# MiL-Driver.net
KiCad netlist of a schematic drawn in EAGLE
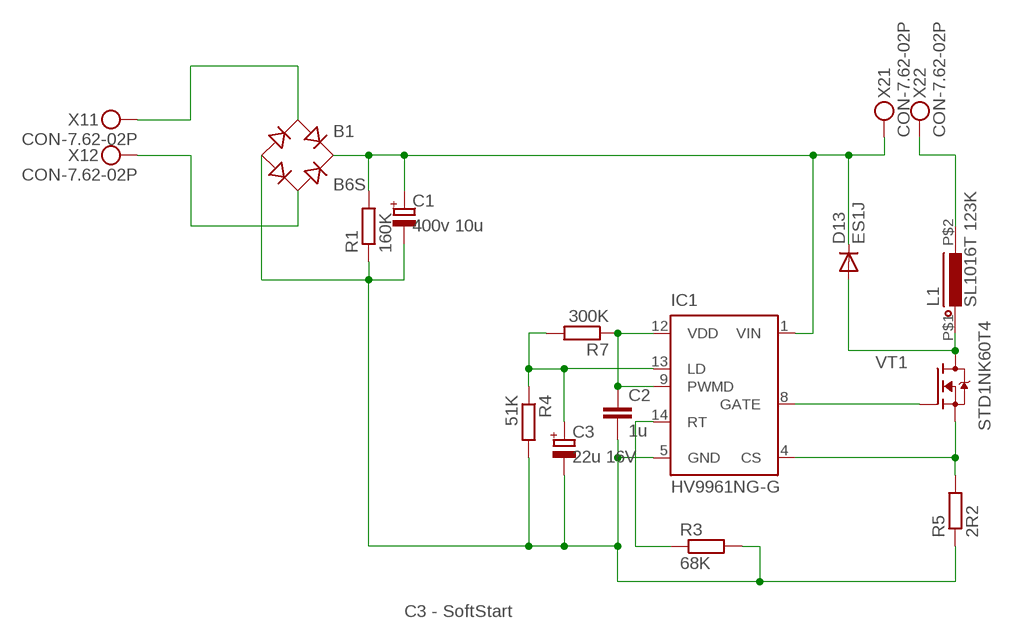
[diagram p0: schematic, sheet 1]

(export (version "E")
  (design (tool "Eeschema 10.0.6"))
  (components
    (comp (ref "B1")
      (value "B6S")
      (footprint "eagle-import:MBS")
      (libsource (lib "eagle-import") (part "BS6"))
    )
    (comp (ref "C1")
      (value "400v 10u")
      (footprint "eagle-import:E3,5-8")
      (libsource (lib "eagle-import") (part "CAP-POL_E3.5-8"))
    )
    (comp (ref "C2")
      (value "1u")
      (footprint "eagle-import:C0805")
      (libsource (lib "eagle-import") (part "CAP_0805"))
    )
    (comp (ref "C3")
      (value "22u 16V")
      (footprint "eagle-import:E2,5-7")
      (libsource (lib "eagle-import") (part "CAP-POL_E2.5-7"))
    )
    (comp (ref "D13")
      (value "ES1J")
      (footprint "eagle-import:DO214AC")
      (libsource (lib "eagle-import") (part "DIODE_ES1J"))
    )
    (comp (ref "IC1")
      (value "HV9961NG-G")
      (footprint "eagle-import:SOIC-16NG")
      (libsource (lib "eagle-import") (part "HV9910BNG"))
    )
    (comp (ref "L1")
      (value "SL1016T 123K")
      (footprint "eagle-import:SL1016")
      (libsource (lib "eagle-import") (part "INDUCTORSL1016"))
    )
    (comp (ref "R1")
      (value "160K")
      (footprint "eagle-import:MF-0125")
      (libsource (lib "eagle-import") (part "R_MF-0125"))
    )
    (comp (ref "R3")
      (value "68K")
      (footprint "eagle-import:R0805")
      (libsource (lib "eagle-import") (part "R_0805"))
    )
    (comp (ref "R4")
      (value "51K")
      (footprint "eagle-import:R0805")
      (libsource (lib "eagle-import") (part "R_0805"))
    )
    (comp (ref "R5")
      (value "2R2")
      (footprint "eagle-import:MF-025")
      (libsource (lib "eagle-import") (part "R_MF-025"))
    )
    (comp (ref "R7")
      (value "300K")
      (footprint "eagle-import:R0805")
      (libsource (lib "eagle-import") (part "R_0805"))
    )
    (comp (ref "VT1")
      (value "STD1NK60T4")
      (footprint "eagle-import:DPAK")
      (libsource (lib "eagle-import") (part "FET-NDPAK"))
    )
    (comp (ref "X1")
      (value "CON-7.62-02P")
      (footprint "eagle-import:KF25C-7.62-02P-13")
      (libsource (lib "eagle-import") (part "CON-7.62-02P"))
    )
    (comp (ref "X2")
      (value "CON-7.62-02P")
      (footprint "eagle-import:KF25C-7.62-02P-13")
      (libsource (lib "eagle-import") (part "CON-7.62-02P"))
    )
  )
  (nets
    (net (code "1") (name "Net-(IC1-CS)") (class "Default")
      (node (ref "IC1") (pin "4") (pinfunction "CS_4") (pintype "input"))
      (node (ref "R5") (pin "2") (pinfunction "2_2") (pintype "passive"))
      (node (ref "VT1") (pin "S") (pinfunction "S_S") (pintype "passive"))
    )
    (net (code "2") (name "Net-(IC1-GATE)") (class "Default")
      (node (ref "IC1") (pin "8") (pinfunction "GATE_8") (pintype "output"))
      (node (ref "VT1") (pin "G") (pinfunction "G_G") (pintype "passive"))
    )
    (net (code "3") (name "Net-(IC1-GND)") (class "Default")
      (node (ref "B1") (pin "-") (pinfunction "-_-") (pintype "passive"))
      (node (ref "C1") (pin "-") (pinfunction "-_-") (pintype "passive"))
      (node (ref "C2") (pin "2") (pinfunction "2_2") (pintype "passive"))
      (node (ref "C3") (pin "-") (pinfunction "-_-") (pintype "passive"))
      (node (ref "IC1") (pin "5") (pinfunction "GND_5") (pintype "power_in"))
      (node (ref "R1") (pin "1") (pinfunction "1_1") (pintype "passive"))
      (node (ref "R3") (pin "2") (pinfunction "2_2") (pintype "passive"))
      (node (ref "R4") (pin "2") (pinfunction "2_2") (pintype "passive"))
      (node (ref "R5") (pin "1") (pinfunction "1_1") (pintype "passive"))
    )
    (net (code "4") (name "Net-(IC1-LD)") (class "Default")
      (node (ref "C3") (pin "+") (pinfunction "+_+") (pintype "passive"))
      (node (ref "IC1") (pin "13") (pinfunction "LD_13") (pintype "input"))
      (node (ref "R4") (pin "1") (pinfunction "1_1") (pintype "passive"))
      (node (ref "R7") (pin "2") (pinfunction "2_2") (pintype "passive"))
    )
    (net (code "5") (name "Net-(IC1-PWMD)") (class "Default")
      (node (ref "C2") (pin "1") (pinfunction "1_1") (pintype "passive"))
      (node (ref "IC1") (pin "12") (pinfunction "VDD_12") (pintype "power_in"))
      (node (ref "IC1") (pin "9") (pinfunction "PWMD_9") (pintype "input"))
      (node (ref "R7") (pin "1") (pinfunction "1_1") (pintype "passive"))
    )
    (net (code "6") (name "Net-(IC1-RT)") (class "Default")
      (node (ref "IC1") (pin "14") (pinfunction "RT_14") (pintype "passive"))
      (node (ref "R3") (pin "1") (pinfunction "1_1") (pintype "passive"))
    )
    (net (code "7") (name "Net-(IC1-VIN)") (class "Default")
      (node (ref "B1") (pin "+") (pinfunction "+_+") (pintype "passive"))
      (node (ref "C1") (pin "+") (pinfunction "+_+") (pintype "passive"))
      (node (ref "D13") (pin "C") (pinfunction "C_C") (pintype "passive"))
      (node (ref "IC1") (pin "1") (pinfunction "VIN_1") (pintype "input"))
      (node (ref "R1") (pin "2") (pinfunction "2_2") (pintype "passive"))
      (node (ref "X2") (pin "P$1") (pinfunction "KL_P$1") (pintype "passive"))
    )
    (net (code "8") (name "Net-(L1-1)") (class "Default")
      (node (ref "D13") (pin "A") (pinfunction "A_A") (pintype "passive"))
      (node (ref "L1") (pin "P$1") (pinfunction "1_P$1") (pintype "passive"))
      (node (ref "VT1") (pin "D") (pinfunction "D_D") (pintype "passive"))
    )
    (net (code "9") (name "Net-(L1-2)") (class "Default")
      (node (ref "L1") (pin "P$2") (pinfunction "2_P$2") (pintype "passive"))
      (node (ref "X2") (pin "P$2") (pinfunction "KL_P$2") (pintype "passive"))
    )
    (net (code "10") (name "Net-(X1A-KL)") (class "Default")
      (node (ref "B1") (pin "AC1") (pinfunction "AC1_AC1") (pintype "passive"))
      (node (ref "X1") (pin "P$1") (pinfunction "KL_P$1") (pintype "passive"))
    )
    (net (code "11") (name "Net-(X1B-KL)") (class "Default")
      (node (ref "B1") (pin "AC2") (pinfunction "AC2_AC2") (pintype "passive"))
      (node (ref "X1") (pin "P$2") (pinfunction "KL_P$2") (pintype "passive"))
    )
  )
)
